# cy18bd103.net
KiCad netlist of a schematic drawn in Altium Designer
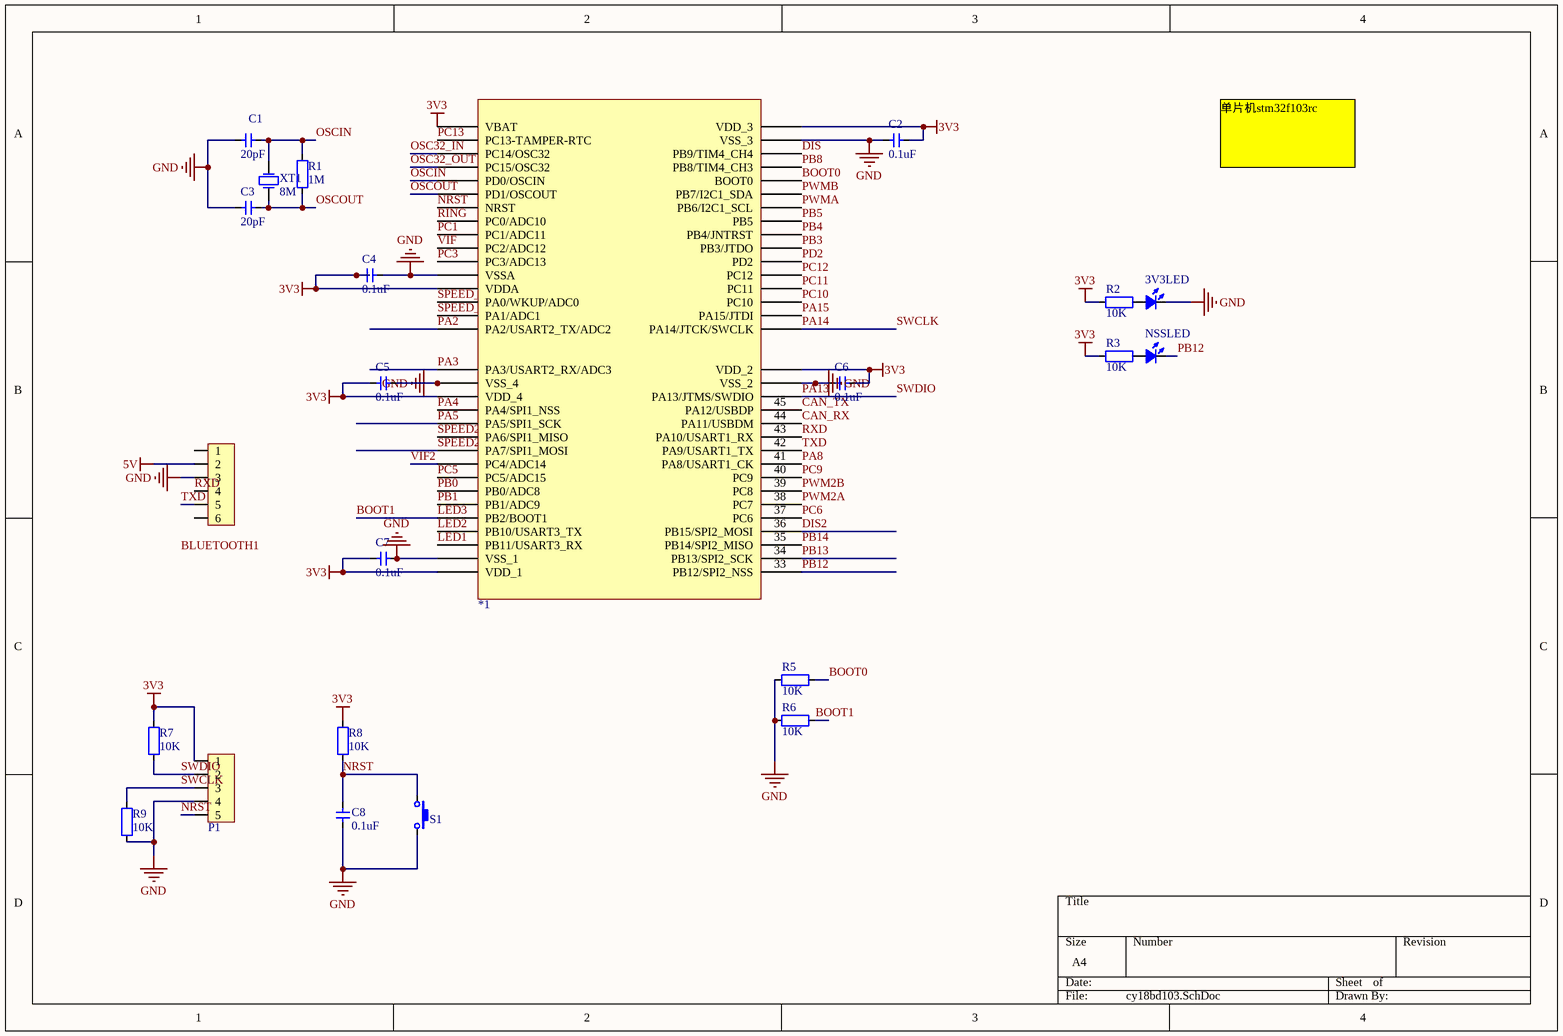
[diagram p0: cy18bd103.SchDoc]

(export (version "E")
  (design (tool "Eeschema 10.0.6"))
  (components
    (comp (ref "*1")
      (value "STM32F103RC")
      (footprint "LQFP_P0.5_64")
      (description "MCU")
      (libsource (lib "Integrated_Library") (part "STM32F103RC"))
    )
    (comp (ref "3V3LED")
      (value "LED_0805blue")
      (footprint "LED_0805_YELLOW")
      (description "LED")
      (libsource (lib "Integrated_Library") (part "LED_0805"))
    )
    (comp (ref "BLUETOOTH1")
      (value "HDR1x6_2.54")
      (footprint "HDR1X6_2.54_180")
      (description "Header")
      (libsource (lib "Integrated_Library") (part "HDR1x6_2.54"))
    )
    (comp (ref "C1")
      (value "20pF")
      (footprint "CAP_0603")
      (description "Capacitor")
      (fields (field (name "Comment") "Cap_0603"))
      (libsource (lib "Integrated_Library") (part "Cap_0603"))
    )
    (comp (ref "C2")
      (value "0.1uF")
      (footprint "CAP_0603")
      (description "Capacitor")
      (fields (field (name "Comment") "Cap_0603"))
      (libsource (lib "Integrated_Library") (part "Cap_0603"))
    )
    (comp (ref "C3")
      (value "20pF")
      (footprint "CAP_0603")
      (description "Capacitor")
      (fields (field (name "Comment") "Cap_0603"))
      (libsource (lib "Integrated_Library") (part "Cap_0603"))
    )
    (comp (ref "C4")
      (value "0.1uF")
      (footprint "CAP_0603")
      (description "Capacitor")
      (fields (field (name "Comment") "Cap_0603"))
      (libsource (lib "Integrated_Library") (part "Cap_0603"))
    )
    (comp (ref "C5")
      (value "0.1uF")
      (footprint "CAP_0603")
      (description "Capacitor")
      (fields (field (name "Comment") "Cap_0603"))
      (libsource (lib "Integrated_Library") (part "Cap_0603"))
    )
    (comp (ref "C6")
      (value "0.1uF")
      (footprint "CAP_0603")
      (description "Capacitor")
      (fields (field (name "Comment") "Cap_0603"))
      (libsource (lib "Integrated_Library") (part "Cap_0603"))
    )
    (comp (ref "C7")
      (value "0.1uF")
      (footprint "CAP_0603")
      (description "Capacitor")
      (fields (field (name "Comment") "Cap_0603"))
      (libsource (lib "Integrated_Library") (part "Cap_0603"))
    )
    (comp (ref "C8")
      (value "0.1uF")
      (footprint "CAP_0603")
      (description "Capacitor")
      (fields (field (name "Comment") "Cap_0603"))
      (libsource (lib "Integrated_Library") (part "Cap_0603"))
    )
    (comp (ref "NSSLED")
      (value "LED_0805green")
      (footprint "LED_0805_GREEN")
      (description "LED")
      (libsource (lib "Integrated_Library") (part "LED_0805"))
    )
    (comp (ref "P1")
      (value "HDR1x5_2.54")
      (footprint "HDR1X5_2.54_180")
      (description "Header")
      (libsource (lib "Integrated_Library") (part "HDR1x5_2.54"))
    )
    (comp (ref "R1")
      (value "1M")
      (footprint "RES_0603")
      (description "Resistor")
      (fields (field (name "Comment") "Res_0603"))
      (libsource (lib "Integrated_Library") (part "Res_0603"))
    )
    (comp (ref "R2")
      (value "10K")
      (footprint "RES_0603")
      (description "Resistor")
      (fields (field (name "Comment") "Res_0603"))
      (libsource (lib "") (part "Res_0603_1"))
    )
    (comp (ref "R3")
      (value "10K")
      (footprint "RES_0603")
      (description "Resistor")
      (fields (field (name "Comment") "Res_0603"))
      (libsource (lib "") (part "Res_0603_1"))
    )
    (comp (ref "R5")
      (value "10K")
      (footprint "RES_0603")
      (description "Resistor")
      (fields (field (name "Comment") "Res_0603"))
      (libsource (lib "") (part "Res_0603_2"))
    )
    (comp (ref "R6")
      (value "10K")
      (footprint "RES_0603")
      (description "Resistor")
      (fields (field (name "Comment") "Res_0603"))
      (libsource (lib "") (part "Res_0603_2"))
    )
    (comp (ref "R7")
      (value "10K")
      (footprint "RES_0603")
      (description "Resistor")
      (fields (field (name "Comment") "Res_0603"))
      (libsource (lib "Integrated_Library") (part "Res_0603"))
    )
    (comp (ref "R8")
      (value "10K")
      (footprint "RES_0603")
      (description "Resistor")
      (fields (field (name "Comment") "Res_0603"))
      (libsource (lib "Integrated_Library") (part "Res_0603"))
    )
    (comp (ref "R9")
      (value "10K")
      (footprint "RES_0603")
      (description "Resistor")
      (fields (field (name "Comment") "Res_0603"))
      (libsource (lib "Integrated_Library") (part "Res_0603"))
    )
    (comp (ref "S1")
      (value "ButtonTACT_3x6x2.5_180")
      (footprint "ButtonTACT_3x6x2.5_180")
      (description "Button")
      (libsource (lib "Integrated_Library") (part "ButtonTACT_3x6x2.5_180"))
    )
    (comp (ref "XT1")
      (value "8M")
      (footprint "XT_5032_2")
      (description "Crystal Oscillator")
      (fields (field (name "Comment") "XTAL_32.768kHz"))
      (libsource (lib "Integrated_Library") (part "XTAL_32.768k"))
    )
  )
  (nets
    (net (code "1") (name "/BOOT0") (class "Default")
      (node (ref "*1") (pin "60") (pinfunction "BOOT0_60") (pintype "passive"))
      (node (ref "R5") (pin "1") (pinfunction "1_1") (pintype "passive"))
    )
    (net (code "2") (name "/BOOT1") (class "Default")
      (node (ref "*1") (pin "28") (pinfunction "PB2/BOOT1_28") (pintype "passive"))
      (node (ref "R6") (pin "1") (pinfunction "1_1") (pintype "passive"))
    )
    (net (code "3") (name "/CAN_RX") (class "Default")
      (node (ref "*1") (pin "44") (pinfunction "PA11/USBDM_44") (pintype "passive"))
    )
    (net (code "4") (name "/CAN_TX") (class "Default")
      (node (ref "*1") (pin "45") (pinfunction "PA12/USBDP_45") (pintype "passive"))
    )
    (net (code "5") (name "/DIS") (class "Default")
      (node (ref "*1") (pin "62") (pinfunction "PB9/TIM4_CH4_62") (pintype "passive"))
    )
    (net (code "6") (name "/DIS2") (class "Default")
      (node (ref "*1") (pin "36") (pinfunction "PB15/SPI2_MOSI_36") (pintype "passive"))
    )
    (net (code "7") (name "/LED1") (class "Default")
      (node (ref "*1") (pin "30") (pinfunction "PB11/USART3_RX_30") (pintype "passive"))
    )
    (net (code "8") (name "/LED2") (class "Default")
      (node (ref "*1") (pin "29") (pinfunction "PB10/USART3_TX_29") (pintype "passive"))
    )
    (net (code "9") (name "/NRST") (class "Default")
      (node (ref "*1") (pin "7") (pinfunction "NRST_7") (pintype "passive"))
      (node (ref "C8") (pin "2") (pinfunction "2_2") (pintype "passive"))
      (node (ref "P1") (pin "5") (pinfunction "5_5") (pintype "passive"))
      (node (ref "R8") (pin "1") (pinfunction "1_1") (pintype "passive"))
      (node (ref "S1") (pin "1") (pinfunction "1_1") (pintype "passive"))
    )
    (net (code "10") (name "/OSC32_IN") (class "Default")
      (node (ref "*1") (pin "3") (pinfunction "PC14/OSC32_3") (pintype "passive"))
    )
    (net (code "11") (name "/OSC32_OUT") (class "Default")
      (node (ref "*1") (pin "4") (pinfunction "PC15/OSC32_4") (pintype "passive"))
    )
    (net (code "12") (name "/OSCIN") (class "Default")
      (node (ref "*1") (pin "5") (pinfunction "PD0/OSCIN_5") (pintype "passive"))
      (node (ref "C1") (pin "2") (pinfunction "2_2") (pintype "passive"))
      (node (ref "R1") (pin "2") (pinfunction "2_2") (pintype "passive"))
      (node (ref "XT1") (pin "2") (pinfunction "OSC2_2") (pintype "passive"))
    )
    (net (code "13") (name "/OSCOUT") (class "Default")
      (node (ref "*1") (pin "6") (pinfunction "PD1/OSCOUT_6") (pintype "passive"))
      (node (ref "C3") (pin "2") (pinfunction "2_2") (pintype "passive"))
      (node (ref "R1") (pin "1") (pinfunction "1_1") (pintype "passive"))
      (node (ref "XT1") (pin "1") (pinfunction "OSC1_1") (pintype "passive"))
    )
    (net (code "14") (name "/PA2") (class "Default")
      (node (ref "*1") (pin "16") (pinfunction "PA2/USART2_TX/ADC2_16") (pintype "passive"))
    )
    (net (code "15") (name "/PA3") (class "Default")
      (node (ref "*1") (pin "17") (pinfunction "PA3/USART2_RX/ADC3_17") (pintype "passive"))
    )
    (net (code "16") (name "/PA4") (class "Default")
      (node (ref "*1") (pin "20") (pinfunction "PA4/SPI1_NSS_20") (pintype "passive"))
    )
    (net (code "17") (name "/PA5") (class "Default")
      (node (ref "*1") (pin "21") (pinfunction "PA5/SPI1_SCK_21") (pintype "passive"))
    )
    (net (code "18") (name "/PA8") (class "Default")
      (node (ref "*1") (pin "41") (pinfunction "PA8/USART1_CK_41") (pintype "passive"))
    )
    (net (code "19") (name "/PA13") (class "Default")
      (node (ref "*1") (pin "46") (pinfunction "PA13/JTMS/SWDIO_46") (pintype "passive"))
      (node (ref "P1") (pin "2") (pinfunction "2_2") (pintype "passive"))
      (node (ref "R7") (pin "1") (pinfunction "1_1") (pintype "passive"))
    )
    (net (code "20") (name "/PA14") (class "Default")
      (node (ref "*1") (pin "49") (pinfunction "PA14/JTCK/SWCLK_49") (pintype "passive"))
      (node (ref "P1") (pin "3") (pinfunction "3_3") (pintype "passive"))
      (node (ref "R9") (pin "2") (pinfunction "2_2") (pintype "passive"))
    )
    (net (code "21") (name "/PA15") (class "Default")
      (node (ref "*1") (pin "50") (pinfunction "PA15/JTDI_50") (pintype "passive"))
    )
    (net (code "22") (name "/PB0") (class "Default")
      (node (ref "*1") (pin "26") (pinfunction "PB0/ADC8_26") (pintype "passive"))
    )
    (net (code "23") (name "/PB1") (class "Default")
      (node (ref "*1") (pin "27") (pinfunction "PB1/ADC9_27") (pintype "passive"))
    )
    (net (code "24") (name "/PB3") (class "Default")
      (node (ref "*1") (pin "55") (pinfunction "PB3/JTDO_55") (pintype "passive"))
    )
    (net (code "25") (name "/PB4") (class "Default")
      (node (ref "*1") (pin "56") (pinfunction "PB4/JNTRST_56") (pintype "passive"))
    )
    (net (code "26") (name "/PB5") (class "Default")
      (node (ref "*1") (pin "57") (pinfunction "PB5_57") (pintype "passive"))
    )
    (net (code "27") (name "/PB8") (class "Default")
      (node (ref "*1") (pin "61") (pinfunction "PB8/TIM4_CH3_61") (pintype "passive"))
    )
    (net (code "28") (name "/PB12") (class "Default")
      (node (ref "*1") (pin "33") (pinfunction "PB12/SPI2_NSS_33") (pintype "passive"))
      (node (ref "NSSLED") (pin "2") (pinfunction "K_2") (pintype "passive"))
    )
    (net (code "29") (name "/PB13") (class "Default")
      (node (ref "*1") (pin "34") (pinfunction "PB13/SPI2_SCK_34") (pintype "passive"))
    )
    (net (code "30") (name "/PB14") (class "Default")
      (node (ref "*1") (pin "35") (pinfunction "PB14/SPI2_MISO_35") (pintype "passive"))
    )
    (net (code "31") (name "/PC1") (class "Default")
      (node (ref "*1") (pin "9") (pinfunction "PC1/ADC11_9") (pintype "passive"))
    )
    (net (code "32") (name "/PC3") (class "Default")
      (node (ref "*1") (pin "11") (pinfunction "PC3/ADC13_11") (pintype "passive"))
    )
    (net (code "33") (name "/PC5") (class "Default")
      (node (ref "*1") (pin "25") (pinfunction "PC5/ADC15_25") (pintype "passive"))
    )
    (net (code "34") (name "/PC6") (class "Default")
      (node (ref "*1") (pin "37") (pinfunction "PC6_37") (pintype "passive"))
    )
    (net (code "35") (name "/PC9") (class "Default")
      (node (ref "*1") (pin "40") (pinfunction "PC9_40") (pintype "passive"))
    )
    (net (code "36") (name "/PC10") (class "Default")
      (node (ref "*1") (pin "51") (pinfunction "PC10_51") (pintype "passive"))
    )
    (net (code "37") (name "/PC11") (class "Default")
      (node (ref "*1") (pin "52") (pinfunction "PC11_52") (pintype "passive"))
    )
    (net (code "38") (name "/PC12") (class "Default")
      (node (ref "*1") (pin "53") (pinfunction "PC12_53") (pintype "passive"))
    )
    (net (code "39") (name "/PC13") (class "Default")
      (node (ref "*1") (pin "2") (pinfunction "PC13-TAMPER-RTC_2") (pintype "passive"))
    )
    (net (code "40") (name "/PD2") (class "Default")
      (node (ref "*1") (pin "54") (pinfunction "PD2_54") (pintype "passive"))
    )
    (net (code "41") (name "/PWM2A") (class "Default")
      (node (ref "*1") (pin "38") (pinfunction "PC7_38") (pintype "passive"))
    )
    (net (code "42") (name "/PWM2B") (class "Default")
      (node (ref "*1") (pin "39") (pinfunction "PC8_39") (pintype "passive"))
    )
    (net (code "43") (name "/PWMA") (class "Default")
      (node (ref "*1") (pin "58") (pinfunction "PB6/I2C1_SCL_58") (pintype "passive"))
    )
    (net (code "44") (name "/PWMB") (class "Default")
      (node (ref "*1") (pin "59") (pinfunction "PB7/I2C1_SDA_59") (pintype "passive"))
    )
    (net (code "45") (name "/RING") (class "Default")
      (node (ref "*1") (pin "8") (pinfunction "PC0/ADC10_8") (pintype "passive"))
    )
    (net (code "46") (name "/RXD") (class "Default")
      (node (ref "*1") (pin "43") (pinfunction "PA10/USART1_RX_43") (pintype "passive"))
      (node (ref "BLUETOOTH1") (pin "4") (pinfunction "4_4") (pintype "passive"))
    )
    (net (code "47") (name "/SPEED2_A") (class "Default")
      (node (ref "*1") (pin "22") (pinfunction "PA6/SPI1_MISO_22") (pintype "passive"))
    )
    (net (code "48") (name "/SPEED2_B") (class "Default")
      (node (ref "*1") (pin "23") (pinfunction "PA7/SPI1_MOSI_23") (pintype "passive"))
    )
    (net (code "49") (name "/SPEED_A") (class "Default")
      (node (ref "*1") (pin "14") (pinfunction "PA0/WKUP/ADC0_14") (pintype "passive"))
    )
    (net (code "50") (name "/SPEED_B") (class "Default")
      (node (ref "*1") (pin "15") (pinfunction "PA1/ADC1_15") (pintype "passive"))
    )
    (net (code "51") (name "/TXD") (class "Default")
      (node (ref "*1") (pin "42") (pinfunction "PA9/USART1_TX_42") (pintype "passive"))
      (node (ref "BLUETOOTH1") (pin "5") (pinfunction "5_5") (pintype "passive"))
    )
    (net (code "52") (name "/VIF") (class "Default")
      (node (ref "*1") (pin "10") (pinfunction "PC2/ADC12_10") (pintype "passive"))
    )
    (net (code "53") (name "/VIF2") (class "Default")
      (node (ref "*1") (pin "24") (pinfunction "PC4/ADC14_24") (pintype "passive"))
    )
    (net (code "54") (name "3V3") (class "Default")
      (node (ref "*1") (pin "1") (pinfunction "VBAT_1") (pintype "passive"))
      (node (ref "*1") (pin "13") (pinfunction "VDDA_13") (pintype "passive"))
      (node (ref "*1") (pin "19") (pinfunction "VDD_4_19") (pintype "passive"))
      (node (ref "*1") (pin "32") (pinfunction "VDD_1_32") (pintype "passive"))
      (node (ref "*1") (pin "48") (pinfunction "VDD_2_48") (pintype "passive"))
      (node (ref "*1") (pin "64") (pinfunction "VDD_3_64") (pintype "passive"))
      (node (ref "C2") (pin "2") (pinfunction "2_2") (pintype "passive"))
      (node (ref "C4") (pin "1") (pinfunction "1_1") (pintype "passive"))
      (node (ref "C5") (pin "1") (pinfunction "1_1") (pintype "passive"))
      (node (ref "C6") (pin "2") (pinfunction "2_2") (pintype "passive"))
      (node (ref "C7") (pin "1") (pinfunction "1_1") (pintype "passive"))
      (node (ref "P1") (pin "1") (pinfunction "1_1") (pintype "passive"))
      (node (ref "R2") (pin "1") (pinfunction "1_1") (pintype "passive"))
      (node (ref "R3") (pin "1") (pinfunction "1_1") (pintype "passive"))
      (node (ref "R7") (pin "2") (pinfunction "2_2") (pintype "passive"))
      (node (ref "R8") (pin "2") (pinfunction "2_2") (pintype "passive"))
    )
    (net (code "55") (name "5V") (class "Default")
      (node (ref "BLUETOOTH1") (pin "2") (pinfunction "2_2") (pintype "passive"))
    )
    (net (code "56") (name "GND") (class "Default")
      (node (ref "*1") (pin "12") (pinfunction "VSSA_12") (pintype "passive"))
      (node (ref "*1") (pin "18") (pinfunction "VSS_4_18") (pintype "passive"))
      (node (ref "*1") (pin "31") (pinfunction "VSS_1_31") (pintype "passive"))
      (node (ref "*1") (pin "47") (pinfunction "VSS_2_47") (pintype "passive"))
      (node (ref "*1") (pin "63") (pinfunction "VSS_3_63") (pintype "passive"))
      (node (ref "3V3LED") (pin "2") (pinfunction "K_2") (pintype "passive"))
      (node (ref "BLUETOOTH1") (pin "3") (pinfunction "3_3") (pintype "passive"))
      (node (ref "C1") (pin "1") (pinfunction "1_1") (pintype "passive"))
      (node (ref "C2") (pin "1") (pinfunction "1_1") (pintype "passive"))
      (node (ref "C3") (pin "1") (pinfunction "1_1") (pintype "passive"))
      (node (ref "C4") (pin "2") (pinfunction "2_2") (pintype "passive"))
      (node (ref "C5") (pin "2") (pinfunction "2_2") (pintype "passive"))
      (node (ref "C6") (pin "1") (pinfunction "1_1") (pintype "passive"))
      (node (ref "C7") (pin "2") (pinfunction "2_2") (pintype "passive"))
      (node (ref "C8") (pin "1") (pinfunction "1_1") (pintype "passive"))
      (node (ref "P1") (pin "4") (pinfunction "4_4") (pintype "passive"))
      (node (ref "R5") (pin "2") (pinfunction "2_2") (pintype "passive"))
      (node (ref "R6") (pin "2") (pinfunction "2_2") (pintype "passive"))
      (node (ref "R9") (pin "1") (pinfunction "1_1") (pintype "passive"))
      (node (ref "S1") (pin "2") (pinfunction "2_2") (pintype "passive"))
    )
    (net (code "57") (name "Net-(3V3LED-A)") (class "Default")
      (node (ref "3V3LED") (pin "1") (pinfunction "A_1") (pintype "passive"))
      (node (ref "R2") (pin "2") (pinfunction "2_2") (pintype "passive"))
    )
    (net (code "58") (name "Net-(NSSLED-A)") (class "Default")
      (node (ref "NSSLED") (pin "1") (pinfunction "A_1") (pintype "passive"))
      (node (ref "R3") (pin "2") (pinfunction "2_2") (pintype "passive"))
    )
    (net (code "59") (name "unconnected-(BLUETOOTH1-Pad1)") (class "Default")
      (node (ref "BLUETOOTH1") (pin "1") (pinfunction "1_1") (pintype "passive"))
    )
    (net (code "60") (name "unconnected-(BLUETOOTH1-Pad6)") (class "Default")
      (node (ref "BLUETOOTH1") (pin "6") (pinfunction "6_6") (pintype "passive"))
    )
  )
)
